# STM32F103ZET6_MinSystem.net
KiCad netlist of a schematic drawn in Altium Designer
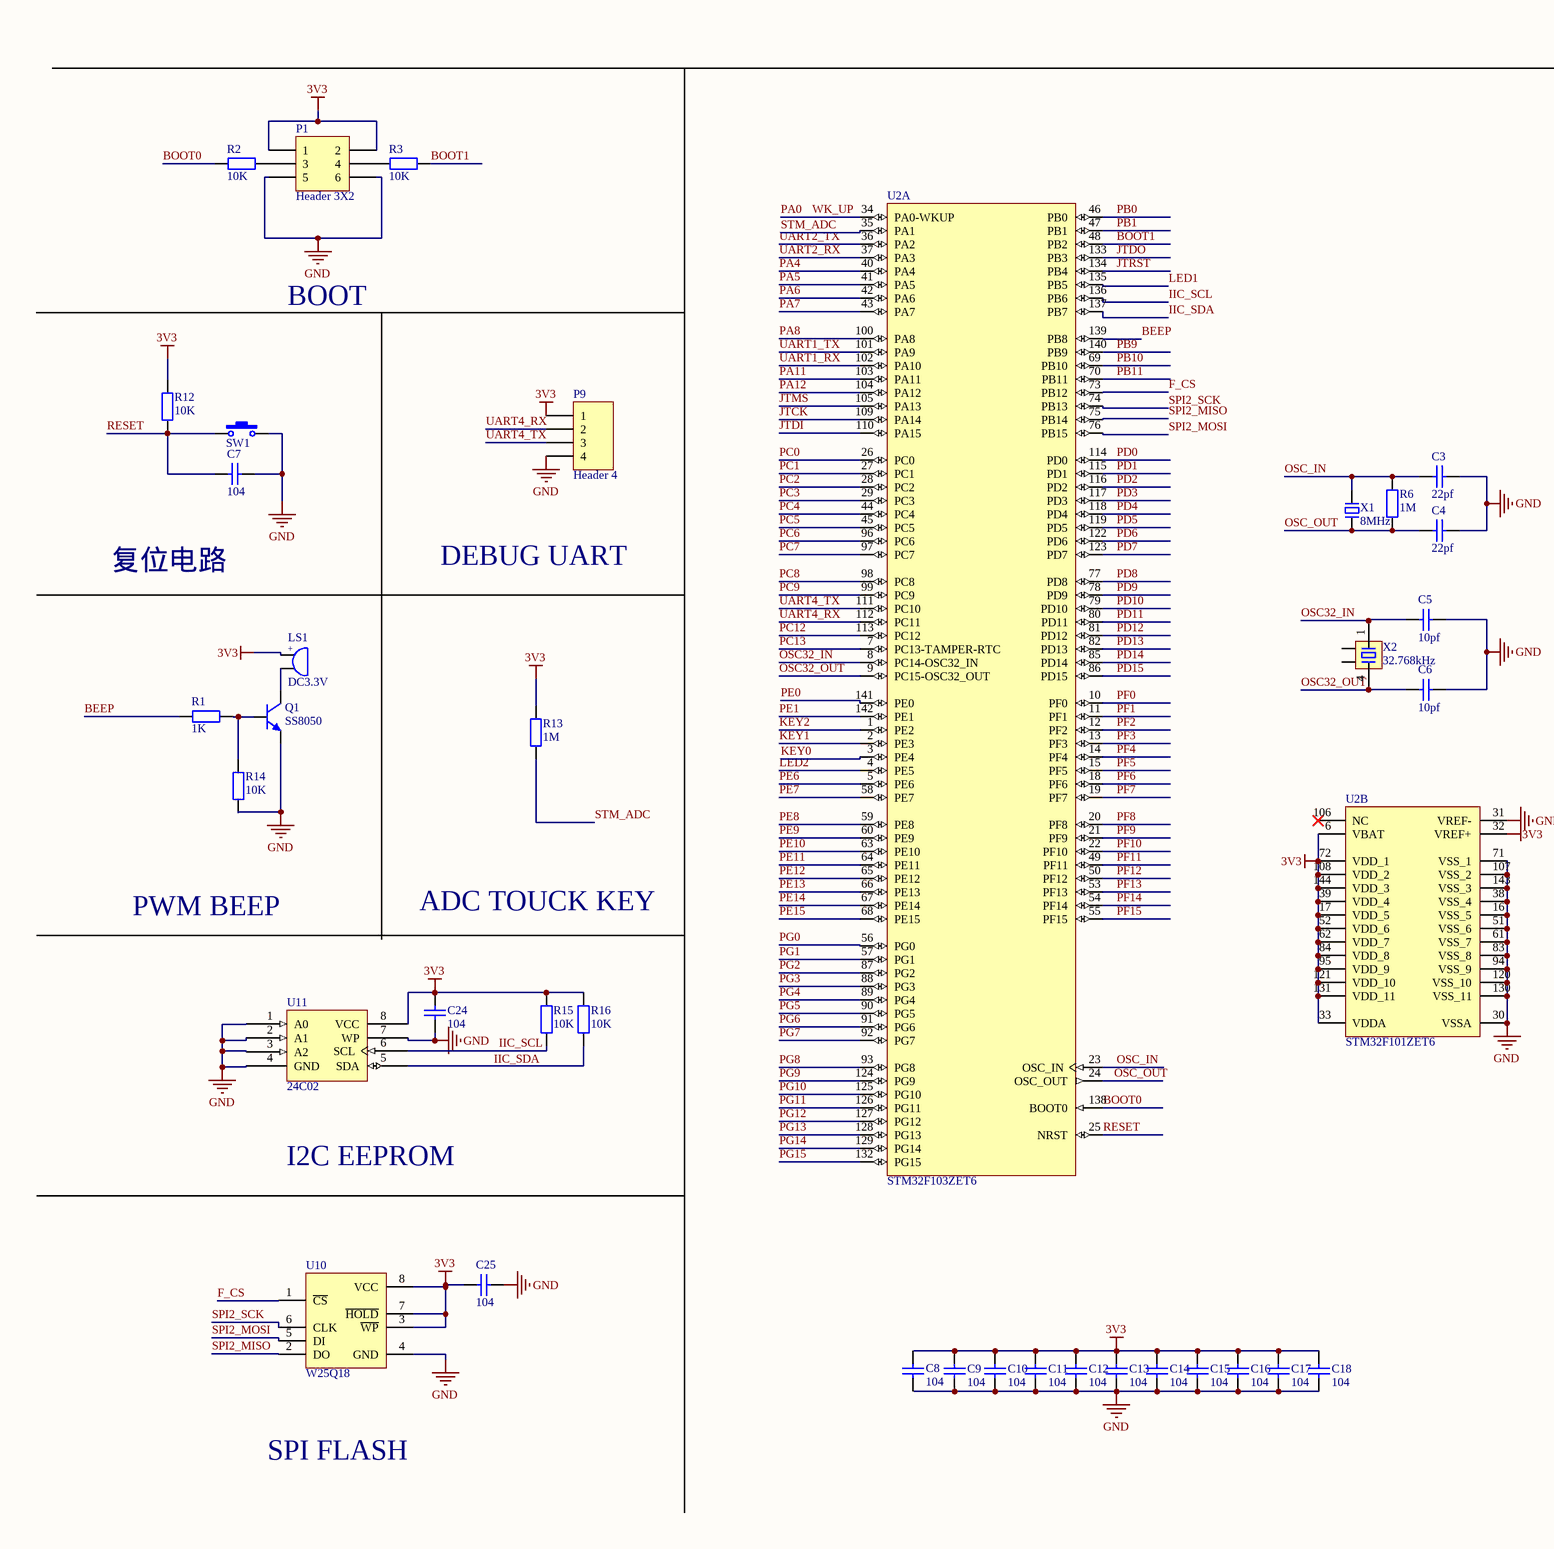
[diagram p0: STM32F103ZET6_MinSystem.SchDoc, left]
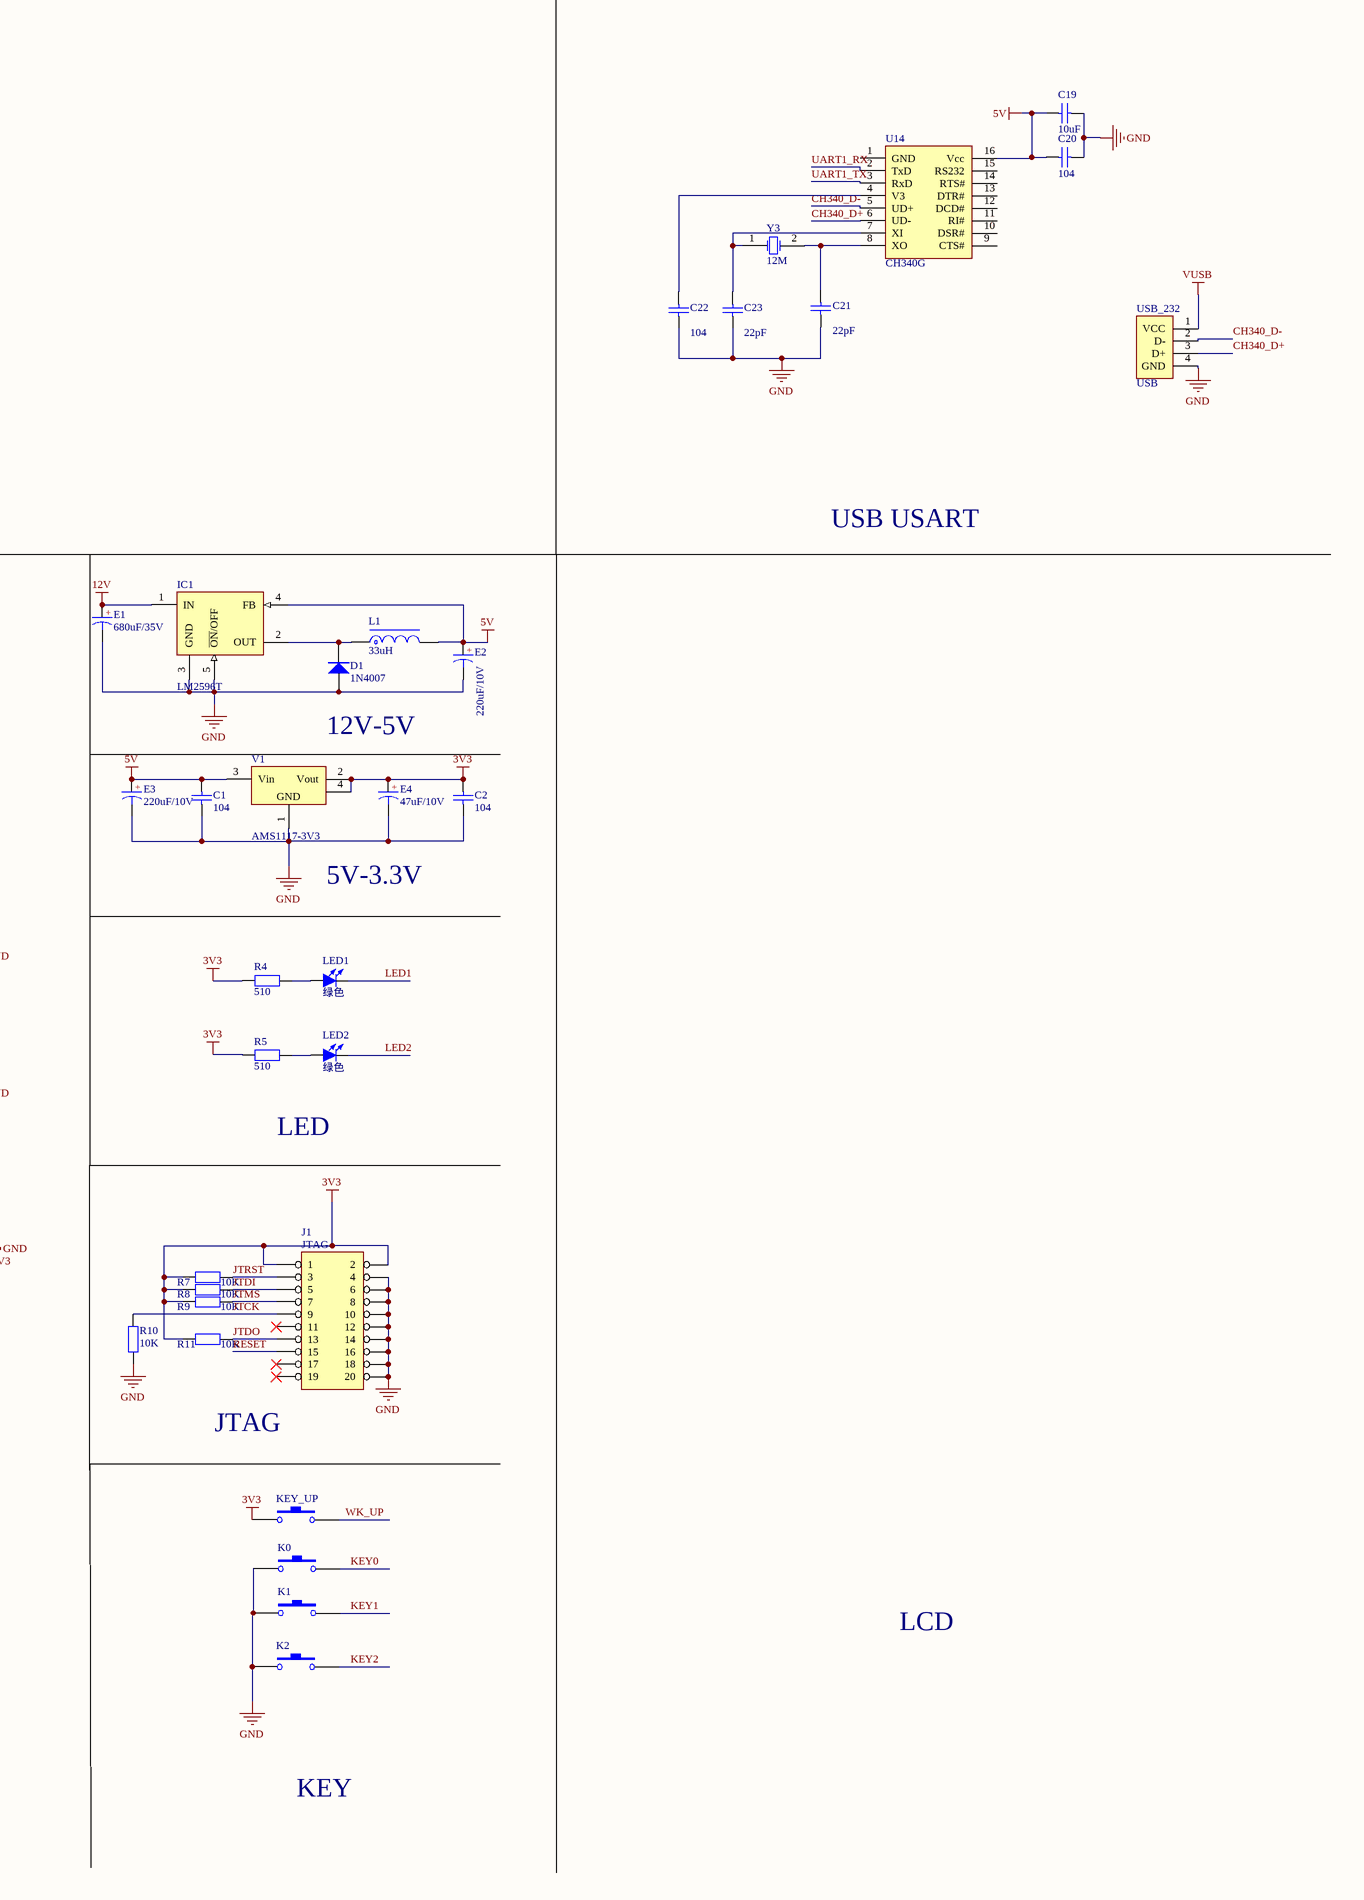
[diagram p1: STM32F103ZET6_MinSystem.SchDoc, right]

(export (version "E")
  (design (tool "Eeschema 10.0.6"))
  (components
    (comp (ref "C1")
      (value "104")
      (footprint "C0603_M")
      (description "贴片电容/MLCC电容")
      (libsource (lib "0.1 - 电阻-电容-电感-晶振-晶体-磁珠-电位器-法拉电容-馈通电容") (part "C"))
    )
    (comp (ref "C2")
      (value "104")
      (footprint "C0603_M")
      (description "贴片电容/MLCC电容")
      (libsource (lib "0.1 - 电阻-电容-电感-晶振-晶体-磁珠-电位器-法拉电容-馈通电容") (part "C"))
    )
    (comp (ref "C3")
      (value "22pf")
      (footprint "C0603_M")
      (description "贴片电容/MLCC电容")
      (libsource (lib "0.1 - 电阻-电容-电感-晶振-晶体-磁珠-电位器-法拉电容-馈通电容") (part "C"))
    )
    (comp (ref "C4")
      (value "22pf")
      (footprint "C0603_M")
      (description "贴片电容/MLCC电容")
      (libsource (lib "0.1 - 电阻-电容-电感-晶振-晶体-磁珠-电位器-法拉电容-馈通电容") (part "C"))
    )
    (comp (ref "C5")
      (value "10pf")
      (footprint "C0603_M")
      (description "贴片电容/MLCC电容")
      (libsource (lib "0.1 - 电阻-电容-电感-晶振-晶体-磁珠-电位器-法拉电容-馈通电容") (part "C"))
    )
    (comp (ref "C6")
      (value "10pf")
      (footprint "C0603_M")
      (description "贴片电容/MLCC电容")
      (libsource (lib "0.1 - 电阻-电容-电感-晶振-晶体-磁珠-电位器-法拉电容-馈通电容") (part "C"))
    )
    (comp (ref "C7")
      (value "104")
      (footprint "C0603_M")
      (description "贴片电容/MLCC电容")
      (libsource (lib "0.1 - 电阻-电容-电感-晶振-晶体-磁珠-电位器-法拉电容-馈通电容") (part "C"))
    )
    (comp (ref "C8")
      (value "104")
      (footprint "C0603_M")
      (description "贴片电容/MLCC电容")
      (libsource (lib "0.1 - 电阻-电容-电感-晶振-晶体-磁珠-电位器-法拉电容-馈通电容") (part "C"))
    )
    (comp (ref "C9")
      (value "104")
      (footprint "C0603_M")
      (description "贴片电容/MLCC电容")
      (libsource (lib "0.1 - 电阻-电容-电感-晶振-晶体-磁珠-电位器-法拉电容-馈通电容") (part "C"))
    )
    (comp (ref "C10")
      (value "104")
      (footprint "C0603_M")
      (description "贴片电容/MLCC电容")
      (libsource (lib "0.1 - 电阻-电容-电感-晶振-晶体-磁珠-电位器-法拉电容-馈通电容") (part "C"))
    )
    (comp (ref "C11")
      (value "104")
      (footprint "C0603_M")
      (description "贴片电容/MLCC电容")
      (libsource (lib "0.1 - 电阻-电容-电感-晶振-晶体-磁珠-电位器-法拉电容-馈通电容") (part "C"))
    )
    (comp (ref "C12")
      (value "104")
      (footprint "C0603_M")
      (description "贴片电容/MLCC电容")
      (libsource (lib "0.1 - 电阻-电容-电感-晶振-晶体-磁珠-电位器-法拉电容-馈通电容") (part "C"))
    )
    (comp (ref "C13")
      (value "104")
      (footprint "C0603_M")
      (description "贴片电容/MLCC电容")
      (libsource (lib "0.1 - 电阻-电容-电感-晶振-晶体-磁珠-电位器-法拉电容-馈通电容") (part "C"))
    )
    (comp (ref "C14")
      (value "104")
      (footprint "C0603_M")
      (description "贴片电容/MLCC电容")
      (libsource (lib "0.1 - 电阻-电容-电感-晶振-晶体-磁珠-电位器-法拉电容-馈通电容") (part "C"))
    )
    (comp (ref "C15")
      (value "104")
      (footprint "C0603_M")
      (description "贴片电容/MLCC电容")
      (libsource (lib "0.1 - 电阻-电容-电感-晶振-晶体-磁珠-电位器-法拉电容-馈通电容") (part "C"))
    )
    (comp (ref "C16")
      (value "104")
      (footprint "C0603_M")
      (description "贴片电容/MLCC电容")
      (libsource (lib "0.1 - 电阻-电容-电感-晶振-晶体-磁珠-电位器-法拉电容-馈通电容") (part "C"))
    )
    (comp (ref "C17")
      (value "104")
      (footprint "C0603_M")
      (description "贴片电容/MLCC电容")
      (libsource (lib "0.1 - 电阻-电容-电感-晶振-晶体-磁珠-电位器-法拉电容-馈通电容") (part "C"))
    )
    (comp (ref "C18")
      (value "104")
      (footprint "C0603_M")
      (description "贴片电容/MLCC电容")
      (libsource (lib "0.1 - 电阻-电容-电感-晶振-晶体-磁珠-电位器-法拉电容-馈通电容") (part "C"))
    )
    (comp (ref "C19")
      (value "10uF")
      (footprint "RAD-0.3")
      (description "Capacitor")
      (fields (field (name "Comment") "Cap") (field (name "PUBLISHER") "Altium Limited"))
      (libsource (lib "Miscellaneous Devices") (part "Cap"))
    )
    (comp (ref "C20")
      (value "104")
      (footprint "RAD-0.3")
      (description "Capacitor")
      (fields (field (name "Comment") "Cap") (field (name "PUBLISHER") "Altium Limited"))
      (libsource (lib "Miscellaneous Devices") (part "Cap"))
    )
    (comp (ref "C21")
      (value "22pF")
      (footprint "RAD-0.3")
      (description "Capacitor")
      (fields (field (name "Comment") "Cap") (field (name "PUBLISHER") "Altium Limited"))
      (libsource (lib "Miscellaneous Devices") (part "Cap"))
    )
    (comp (ref "C22")
      (value "104")
      (footprint "RAD-0.3")
      (description "Capacitor")
      (fields (field (name "Comment") "Cap") (field (name "PUBLISHER") "Altium Limited"))
      (libsource (lib "Miscellaneous Devices") (part "Cap"))
    )
    (comp (ref "C23")
      (value "22pF")
      (footprint "RAD-0.3")
      (description "Capacitor")
      (fields (field (name "Comment") "Cap") (field (name "PUBLISHER") "Altium Limited"))
      (libsource (lib "Miscellaneous Devices") (part "Cap"))
    )
    (comp (ref "C24")
      (value "104")
      (footprint "C0603_M")
      (description "贴片电容/MLCC电容")
      (libsource (lib "0.1 - 电阻-电容-电感-晶振-晶体-磁珠-电位器-法拉电容-馈通电容") (part "C"))
    )
    (comp (ref "C25")
      (value "104")
      (footprint "C0603_M")
      (description "贴片电容/MLCC电容")
      (libsource (lib "0.1 - 电阻-电容-电感-晶振-晶体-磁珠-电位器-法拉电容-馈通电容") (part "C"))
    )
    (comp (ref "D1")
      (value "1N4007")
      (footprint "SMA")
      (description "整流二极管")
      (libsource (lib "0.2 - 二极管-TVS-ESD-整流桥-放电管") (part "1N4007"))
    )
    (comp (ref "E1")
      (value "680uF/35V")
      (footprint "CE G(12.5*13.5)")
      (description "贴片电解电容")
      (libsource (lib "0.1 - 电阻-电容-电感-晶振-晶体-磁珠-电位器-法拉电容-馈通电容") (part "CE_SMD"))
    )
    (comp (ref "E2")
      (value "220uF/10V")
      (footprint "CE D(6.3*7.7)")
      (description "贴片电解电容")
      (libsource (lib "0.1 - 电阻-电容-电感-晶振-晶体-磁珠-电位器-法拉电容-馈通电容") (part "CE_SMD"))
    )
    (comp (ref "E3")
      (value "220uF/10V")
      (footprint "CE D(6.3*7.7)")
      (description "贴片电解电容")
      (libsource (lib "0.1 - 电阻-电容-电感-晶振-晶体-磁珠-电位器-法拉电容-馈通电容") (part "CE_SMD"))
    )
    (comp (ref "E4")
      (value "47uF/10V")
      (footprint "CE B(4*5.4)")
      (description "贴片电解电容")
      (libsource (lib "0.1 - 电阻-电容-电感-晶振-晶体-磁珠-电位器-法拉电容-馈通电容") (part "CE_SMD"))
    )
    (comp (ref "IC1")
      (value "LM2596T")
      (footprint "TO220-5A")
      (description "3A DC-DC降压芯片")
      (libsource (lib "0.7 - 电源类芯片") (part "LM2596T"))
    )
    (comp (ref "J1") (value "JTAG") (footprint "JTAG_20") (libsource (lib "*") (part "HEADER 10X2")))
    (comp (ref "K0")
      (value "SW-PB")
      (footprint "SPST-2")
      (description "Switch")
      (fields (field (name "PUBLISHER") "Altium Limited"))
      (libsource (lib "Miscellaneous Devices") (part "SW-PB"))
    )
    (comp (ref "K1")
      (value "SW-PB")
      (footprint "SPST-2")
      (description "Switch")
      (fields (field (name "PUBLISHER") "Altium Limited"))
      (libsource (lib "Miscellaneous Devices") (part "SW-PB"))
    )
    (comp (ref "K2")
      (value "SW-PB")
      (footprint "SPST-2")
      (description "Switch")
      (fields (field (name "PUBLISHER") "Altium Limited"))
      (libsource (lib "Miscellaneous Devices") (part "SW-PB"))
    )
    (comp (ref "KEY_UP")
      (value "SW-PB")
      (footprint "SPST-2")
      (description "Switch")
      (fields (field (name "PUBLISHER") "Altium Limited"))
      (libsource (lib "Miscellaneous Devices") (part "SW-PB"))
    )
    (comp (ref "L1")
      (value "33uH")
      (footprint "CDRH74")
      (description "CDRH功率屏蔽电感")
      (libsource (lib "0.1 - 电阻-电容-电感-晶振-晶体-磁珠-电位器-法拉电容-馈通电容") (part "L-CDRH"))
    )
    (comp (ref "LED1")
      (value "绿色")
      (footprint "LED0603_G")
      (description "贴片LED")
      (libsource (lib "0.3 - LED发光二极管-IR二极管_接收管-光耦") (part "LED-SMD"))
    )
    (comp (ref "LED2")
      (value "绿色")
      (footprint "LED0603_G")
      (description "贴片LED")
      (libsource (lib "0.3 - LED发光二极管-IR二极管_接收管-光耦") (part "LED-SMD"))
    )
    (comp (ref "LS1")
      (value "DC3.3V")
      (footprint "BEEP 5x9x5.5")
      (description "蜂鸣器")
      (libsource (lib "0.5 - 按键_开关_蜂鸣器_电池_测试点_Mark点_铜柱") (part "BEEP"))
    )
    (comp (ref "P1")
      (value "Header 3X2")
      (footprint "HDR2X3")
      (description "Header, 3-Pin, Dual row")
      (fields (field (name "PUBLISHER") "Altium Limited"))
      (libsource (lib "Miscellaneous Connectors") (part "Header 3X2"))
    )
    (comp (ref "P9")
      (value "Header 4")
      (footprint "HDR1X4")
      (description "Header, 4-Pin")
      (fields (field (name "PUBLISHER") "Altium Limited"))
      (libsource (lib "Miscellaneous Connectors") (part "Header 4"))
    )
    (comp (ref "Q1")
      (value "SS8050")
      (footprint "SOT23-3N")
      (description "高频放大-NPN型")
      (libsource (lib "0.4 - 三极管-场效应管-可控硅") (part "8050-SMD"))
    )
    (comp (ref "R1")
      (value "1K")
      (footprint "R0603_L")
      (description "贴片电阻")
      (libsource (lib "0.1 - 电阻-电容-电感-晶振-晶体-磁珠-电位器-法拉电容-馈通电容") (part "R"))
    )
    (comp (ref "R2")
      (value "10K")
      (footprint "R0603_L")
      (description "贴片电阻")
      (libsource (lib "0.1 - 电阻-电容-电感-晶振-晶体-磁珠-电位器-法拉电容-馈通电容") (part "R"))
    )
    (comp (ref "R3")
      (value "10K")
      (footprint "R0603_L")
      (description "贴片电阻")
      (libsource (lib "0.1 - 电阻-电容-电感-晶振-晶体-磁珠-电位器-法拉电容-馈通电容") (part "R"))
    )
    (comp (ref "R4")
      (value "510")
      (footprint "R0603_L")
      (description "贴片电阻")
      (libsource (lib "0.1 - 电阻-电容-电感-晶振-晶体-磁珠-电位器-法拉电容-馈通电容") (part "R"))
    )
    (comp (ref "R5")
      (value "510")
      (footprint "R0603_L")
      (description "贴片电阻")
      (libsource (lib "0.1 - 电阻-电容-电感-晶振-晶体-磁珠-电位器-法拉电容-馈通电容") (part "R"))
    )
    (comp (ref "R6")
      (value "1M")
      (footprint "R0603_L")
      (description "贴片电阻")
      (libsource (lib "0.1 - 电阻-电容-电感-晶振-晶体-磁珠-电位器-法拉电容-馈通电容") (part "R"))
    )
    (comp (ref "R7")
      (value "10K")
      (footprint "R0603_L")
      (description "贴片电阻")
      (libsource (lib "0.1 - 电阻-电容-电感-晶振-晶体-磁珠-电位器-法拉电容-馈通电容") (part "R"))
    )
    (comp (ref "R8")
      (value "10K")
      (footprint "R0603_L")
      (description "贴片电阻")
      (libsource (lib "0.1 - 电阻-电容-电感-晶振-晶体-磁珠-电位器-法拉电容-馈通电容") (part "R"))
    )
    (comp (ref "R9")
      (value "10K")
      (footprint "R0603_L")
      (description "贴片电阻")
      (libsource (lib "0.1 - 电阻-电容-电感-晶振-晶体-磁珠-电位器-法拉电容-馈通电容") (part "R"))
    )
    (comp (ref "R10")
      (value "10K")
      (footprint "R0603_L")
      (description "贴片电阻")
      (libsource (lib "0.1 - 电阻-电容-电感-晶振-晶体-磁珠-电位器-法拉电容-馈通电容") (part "R"))
    )
    (comp (ref "R11")
      (value "10K")
      (footprint "R0603_L")
      (description "贴片电阻")
      (libsource (lib "0.1 - 电阻-电容-电感-晶振-晶体-磁珠-电位器-法拉电容-馈通电容") (part "R"))
    )
    (comp (ref "R12")
      (value "10K")
      (footprint "R0603_L")
      (description "贴片电阻")
      (libsource (lib "0.1 - 电阻-电容-电感-晶振-晶体-磁珠-电位器-法拉电容-馈通电容") (part "R"))
    )
    (comp (ref "R13")
      (value "1M")
      (footprint "R0603_L")
      (description "贴片电阻")
      (libsource (lib "0.1 - 电阻-电容-电感-晶振-晶体-磁珠-电位器-法拉电容-馈通电容") (part "R"))
    )
    (comp (ref "R14")
      (value "10K")
      (footprint "R0603_L")
      (description "贴片电阻")
      (libsource (lib "0.1 - 电阻-电容-电感-晶振-晶体-磁珠-电位器-法拉电容-馈通电容") (part "R"))
    )
    (comp (ref "R15")
      (value "10K")
      (footprint "R0603_L")
      (description "贴片电阻")
      (libsource (lib "0.1 - 电阻-电容-电感-晶振-晶体-磁珠-电位器-法拉电容-馈通电容") (part "R"))
    )
    (comp (ref "R16")
      (value "10K")
      (footprint "R0603_L")
      (description "贴片电阻")
      (libsource (lib "0.1 - 电阻-电容-电感-晶振-晶体-磁珠-电位器-法拉电容-馈通电容") (part "R"))
    )
    (comp (ref "SW1")
      (value "3x6x5")
      (footprint "SW SMD-3*6*2.5")
      (description "微动开关")
      (libsource (lib "0.5 - 按键_开关_蜂鸣器_保险丝_电池_测试点_Mark点_铜柱") (part "SW-PB"))
    )
    (comp (ref "U2")
      (value "STM32F103ZET6")
      (footprint "LQFP144_N")
      (libsource (lib "2.4 - STM32 F1系列单片机") (part "STM32F101ZET6"))
    )
    (comp (ref "U10")
      (value "W25Q18")
      (footprint "SOP8W_N")
      (description "SPI Flash")
      (libsource (lib "0.8 - 常见芯片") (part "W25Q"))
    )
    (comp (ref "U11")
      (value "24C02")
      (footprint "SOP8_L")
      (description "外置EEPROM")
      (libsource (lib "0.8 - 常见芯片") (part "24Cxx"))
    )
    (comp (ref "U14")
      (value "CH340G")
      (footprint "SOP16_L")
      (description "USB转串口芯片，外置晶振")
      (libsource (lib "0.8 - 常见芯片") (part "CH340G"))
    )
    (comp (ref "USB_232")
      (value "USB")
      (footprint "USB2.0_TYPE-B")
      (description "USB2.0_Type-B母座")
      (libsource (lib "0.6 - 电源_音频_USB Type-C_HDMI_XT60_5557_D-SUB_RJ45_SD-TF_SIM插座") (part "USB2.0_Type-B"))
    )
    (comp (ref "V1")
      (value "AMS1117-3V3")
      (footprint "SOT223_L")
      (description "三端稳压芯片")
      (libsource (lib "0.7 - 电源类芯片") (part "AMS1117"))
    )
    (comp (ref "X1")
      (value "8MHz")
      (footprint "HC-49S")
      (description "2脚无源晶振(谐振器）")
      (libsource (lib "0.1 - 电阻-电容-电感-晶振-晶体-磁珠-电位器-法拉电容-馈通电容") (part "XTAL-2P"))
    )
    (comp (ref "X2")
      (value "32.768kHz")
      (footprint "MC-306")
      (description "MC系列4脚无源晶振(谐振器）")
      (libsource (lib "0.1 - 电阻-电容-电感-晶振-晶体-磁珠-电位器-法拉电容-馈通电容") (part "XTAL-MC-4P"))
    )
    (comp (ref "Y3")
      (value "12M")
      (footprint "R38")
      (description "Crystal Oscillator")
      (fields (field (name "PUBLISHER") "Altium Limited"))
      (libsource (lib "Miscellaneous Devices") (part "XTAL"))
    )
  )
  (nets
    (net (code "1") (name "/BEEP") (class "Default")
      (node (ref "R1") (pin "2") (pinfunction "2_2") (pintype "passive"))
      (node (ref "U2") (pin "139") (pinfunction "PB8_139") (pintype "bidirectional"))
    )
    (net (code "2") (name "/BOOT0") (class "Default")
      (node (ref "R2") (pin "1") (pinfunction "1_1") (pintype "passive"))
      (node (ref "U2") (pin "138") (pinfunction "BOOT0_138") (pintype "input"))
    )
    (net (code "3") (name "/BOOT1") (class "Default")
      (node (ref "R3") (pin "1") (pinfunction "1_1") (pintype "passive"))
      (node (ref "U2") (pin "48") (pinfunction "PB2_48") (pintype "bidirectional"))
    )
    (net (code "4") (name "/CH340_D+") (class "Default")
      (node (ref "U14") (pin "6") (pinfunction "UD-_6") (pintype "passive"))
      (node (ref "USB_232") (pin "3") (pinfunction "D+_3") (pintype "passive"))
    )
    (net (code "5") (name "/CH340_D-") (class "Default")
      (node (ref "U14") (pin "5") (pinfunction "UD+_5") (pintype "passive"))
      (node (ref "USB_232") (pin "2") (pinfunction "D-_2") (pintype "passive"))
    )
    (net (code "6") (name "/F_CS") (class "Default")
      (node (ref "U10") (pin "1") (pinfunction "~{CS}_1") (pintype "passive"))
      (node (ref "U2") (pin "73") (pinfunction "PB12_73") (pintype "bidirectional"))
    )
    (net (code "7") (name "/IIC_SCL") (class "Default")
      (node (ref "R15") (pin "1") (pinfunction "1_1") (pintype "passive"))
      (node (ref "U11") (pin "6") (pinfunction "SCL_6") (pintype "input"))
      (node (ref "U2") (pin "136") (pinfunction "PB6_136") (pintype "bidirectional"))
    )
    (net (code "8") (name "/IIC_SDA") (class "Default")
      (node (ref "U2") (pin "137") (pinfunction "PB7_137") (pintype "bidirectional"))
    )
    (net (code "9") (name "/JTCK") (class "Default")
      (node (ref "J1") (pin "9") (pinfunction "9_9") (pintype "passive"))
      (node (ref "R10") (pin "2") (pinfunction "2_2") (pintype "passive"))
      (node (ref "U2") (pin "109") (pinfunction "PA14_109") (pintype "bidirectional"))
    )
    (net (code "10") (name "/JTDI") (class "Default")
      (node (ref "J1") (pin "5") (pinfunction "5_5") (pintype "passive"))
      (node (ref "R8") (pin "2") (pinfunction "2_2") (pintype "passive"))
      (node (ref "U2") (pin "110") (pinfunction "PA15_110") (pintype "bidirectional"))
    )
    (net (code "11") (name "/JTDO") (class "Default")
      (node (ref "J1") (pin "13") (pinfunction "13_13") (pintype "passive"))
      (node (ref "R11") (pin "2") (pinfunction "2_2") (pintype "passive"))
      (node (ref "U2") (pin "133") (pinfunction "PB3_133") (pintype "bidirectional"))
    )
    (net (code "12") (name "/JTMS") (class "Default")
      (node (ref "J1") (pin "7") (pinfunction "7_7") (pintype "passive"))
      (node (ref "R9") (pin "2") (pinfunction "2_2") (pintype "passive"))
      (node (ref "U2") (pin "105") (pinfunction "PA13_105") (pintype "bidirectional"))
    )
    (net (code "13") (name "/JTRST") (class "Default")
      (node (ref "J1") (pin "3") (pinfunction "3_3") (pintype "passive"))
      (node (ref "R7") (pin "2") (pinfunction "2_2") (pintype "passive"))
      (node (ref "U2") (pin "134") (pinfunction "PB4_134") (pintype "bidirectional"))
    )
    (net (code "14") (name "/KEY0") (class "Default")
      (node (ref "K0") (pin "2") (pinfunction "2_2") (pintype "passive"))
      (node (ref "U2") (pin "3") (pinfunction "PE4_3") (pintype "bidirectional"))
    )
    (net (code "15") (name "/KEY1") (class "Default")
      (node (ref "K1") (pin "2") (pinfunction "2_2") (pintype "passive"))
      (node (ref "U2") (pin "2") (pinfunction "PE3_2") (pintype "bidirectional"))
    )
    (net (code "16") (name "/KEY2") (class "Default")
      (node (ref "K2") (pin "2") (pinfunction "2_2") (pintype "passive"))
      (node (ref "U2") (pin "1") (pinfunction "PE2_1") (pintype "bidirectional"))
    )
    (net (code "17") (name "/LED1") (class "Default")
      (node (ref "LED1") (pin "2") (pinfunction "K_2") (pintype "passive"))
      (node (ref "U2") (pin "135") (pinfunction "PB5_135") (pintype "bidirectional"))
    )
    (net (code "18") (name "/LED2") (class "Default")
      (node (ref "LED2") (pin "2") (pinfunction "K_2") (pintype "passive"))
      (node (ref "U2") (pin "4") (pinfunction "PE5_4") (pintype "bidirectional"))
    )
    (net (code "19") (name "/OSC32_IN") (class "Default")
      (node (ref "C5") (pin "1") (pinfunction "1_1") (pintype "passive"))
      (node (ref "U2") (pin "8") (pinfunction "PC14-OSC32_IN_8") (pintype "bidirectional"))
      (node (ref "X2") (pin "1") (pinfunction "1_1") (pintype "passive"))
    )
    (net (code "20") (name "/OSC32_OUT") (class "Default")
      (node (ref "C6") (pin "1") (pinfunction "1_1") (pintype "passive"))
      (node (ref "U2") (pin "9") (pinfunction "PC15-OSC32_OUT_9") (pintype "bidirectional"))
      (node (ref "X2") (pin "4") (pinfunction "4_4") (pintype "passive"))
    )
    (net (code "21") (name "/OSC_IN") (class "Default")
      (node (ref "C3") (pin "1") (pinfunction "1_1") (pintype "passive"))
      (node (ref "R6") (pin "2") (pinfunction "2_2") (pintype "passive"))
      (node (ref "U2") (pin "23") (pinfunction "OSC_IN_23") (pintype "input"))
      (node (ref "X1") (pin "1") (pinfunction "1_1") (pintype "passive"))
    )
    (net (code "22") (name "/OSC_OUT") (class "Default")
      (node (ref "C4") (pin "1") (pinfunction "1_1") (pintype "passive"))
      (node (ref "R6") (pin "1") (pinfunction "1_1") (pintype "passive"))
      (node (ref "U2") (pin "24") (pinfunction "OSC_OUT_24") (pintype "output"))
      (node (ref "X1") (pin "2") (pinfunction "2_2") (pintype "passive"))
    )
    (net (code "23") (name "/PA0") (class "Default")
      (node (ref "KEY_UP") (pin "2") (pinfunction "2_2") (pintype "passive"))
      (node (ref "U2") (pin "34") (pinfunction "PA0-WKUP_34") (pintype "bidirectional"))
    )
    (net (code "24") (name "/PA4") (class "Default")
      (node (ref "U2") (pin "40") (pinfunction "PA4_40") (pintype "bidirectional"))
    )
    (net (code "25") (name "/PA5") (class "Default")
      (node (ref "U2") (pin "41") (pinfunction "PA5_41") (pintype "bidirectional"))
    )
    (net (code "26") (name "/PA6") (class "Default")
      (node (ref "U2") (pin "42") (pinfunction "PA6_42") (pintype "bidirectional"))
    )
    (net (code "27") (name "/PA7") (class "Default")
      (node (ref "U2") (pin "43") (pinfunction "PA7_43") (pintype "bidirectional"))
    )
    (net (code "28") (name "/PA8") (class "Default")
      (node (ref "U2") (pin "100") (pinfunction "PA8_100") (pintype "bidirectional"))
    )
    (net (code "29") (name "/PA11") (class "Default")
      (node (ref "U2") (pin "103") (pinfunction "PA11_103") (pintype "bidirectional"))
    )
    (net (code "30") (name "/PA12") (class "Default")
      (node (ref "U2") (pin "104") (pinfunction "PA12_104") (pintype "bidirectional"))
    )
    (net (code "31") (name "/PB0") (class "Default")
      (node (ref "U2") (pin "46") (pinfunction "PB0_46") (pintype "bidirectional"))
    )
    (net (code "32") (name "/PB1") (class "Default")
      (node (ref "U2") (pin "47") (pinfunction "PB1_47") (pintype "bidirectional"))
    )
    (net (code "33") (name "/PB9") (class "Default")
      (node (ref "U2") (pin "140") (pinfunction "PB9_140") (pintype "bidirectional"))
    )
    (net (code "34") (name "/PB10") (class "Default")
      (node (ref "U2") (pin "69") (pinfunction "PB10_69") (pintype "bidirectional"))
    )
    (net (code "35") (name "/PB11") (class "Default")
      (node (ref "U2") (pin "70") (pinfunction "PB11_70") (pintype "bidirectional"))
    )
    (net (code "36") (name "/PC0") (class "Default")
      (node (ref "U2") (pin "26") (pinfunction "PC0_26") (pintype "bidirectional"))
    )
    (net (code "37") (name "/PC1") (class "Default")
      (node (ref "U2") (pin "27") (pinfunction "PC1_27") (pintype "bidirectional"))
    )
    (net (code "38") (name "/PC2") (class "Default")
      (node (ref "U2") (pin "28") (pinfunction "PC2_28") (pintype "bidirectional"))
    )
    (net (code "39") (name "/PC3") (class "Default")
      (node (ref "U2") (pin "29") (pinfunction "PC3_29") (pintype "bidirectional"))
    )
    (net (code "40") (name "/PC4") (class "Default")
      (node (ref "U2") (pin "44") (pinfunction "PC4_44") (pintype "bidirectional"))
    )
    (net (code "41") (name "/PC5") (class "Default")
      (node (ref "U2") (pin "45") (pinfunction "PC5_45") (pintype "bidirectional"))
    )
    (net (code "42") (name "/PC6") (class "Default")
      (node (ref "U2") (pin "96") (pinfunction "PC6_96") (pintype "bidirectional"))
    )
    (net (code "43") (name "/PC7") (class "Default")
      (node (ref "U2") (pin "97") (pinfunction "PC7_97") (pintype "bidirectional"))
    )
    (net (code "44") (name "/PC8") (class "Default")
      (node (ref "U2") (pin "98") (pinfunction "PC8_98") (pintype "bidirectional"))
    )
    (net (code "45") (name "/PC9") (class "Default")
      (node (ref "U2") (pin "99") (pinfunction "PC9_99") (pintype "bidirectional"))
    )
    (net (code "46") (name "/PC12") (class "Default")
      (node (ref "U2") (pin "113") (pinfunction "PC12_113") (pintype "bidirectional"))
    )
    (net (code "47") (name "/PC13") (class "Default")
      (node (ref "U2") (pin "7") (pinfunction "PC13-TAMPER-RTC_7") (pintype "bidirectional"))
    )
    (net (code "48") (name "/PD0") (class "Default")
      (node (ref "U2") (pin "114") (pinfunction "PD0_114") (pintype "bidirectional"))
    )
    (net (code "49") (name "/PD1") (class "Default")
      (node (ref "U2") (pin "115") (pinfunction "PD1_115") (pintype "bidirectional"))
    )
    (net (code "50") (name "/PD2") (class "Default")
      (node (ref "U2") (pin "116") (pinfunction "PD2_116") (pintype "bidirectional"))
    )
    (net (code "51") (name "/PD3") (class "Default")
      (node (ref "U2") (pin "117") (pinfunction "PD3_117") (pintype "bidirectional"))
    )
    (net (code "52") (name "/PD4") (class "Default")
      (node (ref "U2") (pin "118") (pinfunction "PD4_118") (pintype "bidirectional"))
    )
    (net (code "53") (name "/PD5") (class "Default")
      (node (ref "U2") (pin "119") (pinfunction "PD5_119") (pintype "bidirectional"))
    )
    (net (code "54") (name "/PD6") (class "Default")
      (node (ref "U2") (pin "122") (pinfunction "PD6_122") (pintype "bidirectional"))
    )
    (net (code "55") (name "/PD7") (class "Default")
      (node (ref "U2") (pin "123") (pinfunction "PD7_123") (pintype "bidirectional"))
    )
    (net (code "56") (name "/PD8") (class "Default")
      (node (ref "U2") (pin "77") (pinfunction "PD8_77") (pintype "bidirectional"))
    )
    (net (code "57") (name "/PD9") (class "Default")
      (node (ref "U2") (pin "78") (pinfunction "PD9_78") (pintype "bidirectional"))
    )
    (net (code "58") (name "/PD10") (class "Default")
      (node (ref "U2") (pin "79") (pinfunction "PD10_79") (pintype "bidirectional"))
    )
    (net (code "59") (name "/PD11") (class "Default")
      (node (ref "U2") (pin "80") (pinfunction "PD11_80") (pintype "bidirectional"))
    )
    (net (code "60") (name "/PD12") (class "Default")
      (node (ref "U2") (pin "81") (pinfunction "PD12_81") (pintype "bidirectional"))
    )
    (net (code "61") (name "/PD13") (class "Default")
      (node (ref "U2") (pin "82") (pinfunction "PD13_82") (pintype "bidirectional"))
    )
    (net (code "62") (name "/PD14") (class "Default")
      (node (ref "U2") (pin "85") (pinfunction "PD14_85") (pintype "bidirectional"))
    )
    (net (code "63") (name "/PD15") (class "Default")
      (node (ref "U2") (pin "86") (pinfunction "PD15_86") (pintype "bidirectional"))
    )
    (net (code "64") (name "/PE0") (class "Default")
      (node (ref "U2") (pin "141") (pinfunction "PE0_141") (pintype "bidirectional"))
    )
    (net (code "65") (name "/PE1") (class "Default")
      (node (ref "U2") (pin "142") (pinfunction "PE1_142") (pintype "bidirectional"))
    )
    (net (code "66") (name "/PE6") (class "Default")
      (node (ref "U2") (pin "5") (pinfunction "PE6_5") (pintype "bidirectional"))
    )
    (net (code "67") (name "/PE7") (class "Default")
      (node (ref "U2") (pin "58") (pinfunction "PE7_58") (pintype "bidirectional"))
    )
    (net (code "68") (name "/PE8") (class "Default")
      (node (ref "U2") (pin "59") (pinfunction "PE8_59") (pintype "bidirectional"))
    )
    (net (code "69") (name "/PE9") (class "Default")
      (node (ref "U2") (pin "60") (pinfunction "PE9_60") (pintype "bidirectional"))
    )
    (net (code "70") (name "/PE10") (class "Default")
      (node (ref "U2") (pin "63") (pinfunction "PE10_63") (pintype "bidirectional"))
    )
    (net (code "71") (name "/PE11") (class "Default")
      (node (ref "U2") (pin "64") (pinfunction "PE11_64") (pintype "bidirectional"))
    )
    (net (code "72") (name "/PE12") (class "Default")
      (node (ref "U2") (pin "65") (pinfunction "PE12_65") (pintype "bidirectional"))
    )
    (net (code "73") (name "/PE13") (class "Default")
      (node (ref "U2") (pin "66") (pinfunction "PE13_66") (pintype "bidirectional"))
    )
    (net (code "74") (name "/PE14") (class "Default")
      (node (ref "U2") (pin "67") (pinfunction "PE14_67") (pintype "bidirectional"))
    )
    (net (code "75") (name "/PE15") (class "Default")
      (node (ref "U2") (pin "68") (pinfunction "PE15_68") (pintype "bidirectional"))
    )
    (net (code "76") (name "/PF0") (class "Default")
      (node (ref "U2") (pin "10") (pinfunction "PF0_10") (pintype "bidirectional"))
    )
    (net (code "77") (name "/PF1") (class "Default")
      (node (ref "U2") (pin "11") (pinfunction "PF1_11") (pintype "bidirectional"))
    )
    (net (code "78") (name "/PF2") (class "Default")
      (node (ref "U2") (pin "12") (pinfunction "PF2_12") (pintype "bidirectional"))
    )
    (net (code "79") (name "/PF3") (class "Default")
      (node (ref "U2") (pin "13") (pinfunction "PF3_13") (pintype "bidirectional"))
    )
    (net (code "80") (name "/PF4") (class "Default")
      (node (ref "U2") (pin "14") (pinfunction "PF4_14") (pintype "bidirectional"))
    )
    (net (code "81") (name "/PF5") (class "Default")
      (node (ref "U2") (pin "15") (pinfunction "PF5_15") (pintype "bidirectional"))
    )
    (net (code "82") (name "/PF6") (class "Default")
      (node (ref "U2") (pin "18") (pinfunction "PF6_18") (pintype "bidirectional"))
    )
    (net (code "83") (name "/PF7") (class "Default")
      (node (ref "U2") (pin "19") (pinfunction "PF7_19") (pintype "bidirectional"))
    )
    (net (code "84") (name "/PF8") (class "Default")
      (node (ref "U2") (pin "20") (pinfunction "PF8_20") (pintype "bidirectional"))
    )
    (net (code "85") (name "/PF9") (class "Default")
      (node (ref "U2") (pin "21") (pinfunction "PF9_21") (pintype "bidirectional"))
    )
    (net (code "86") (name "/PF10") (class "Default")
      (node (ref "U2") (pin "22") (pinfunction "PF10_22") (pintype "bidirectional"))
    )
    (net (code "87") (name "/PF11") (class "Default")
      (node (ref "U2") (pin "49") (pinfunction "PF11_49") (pintype "bidirectional"))
    )
    (net (code "88") (name "/PF12") (class "Default")
      (node (ref "U2") (pin "50") (pinfunction "PF12_50") (pintype "bidirectional"))
    )
    (net (code "89") (name "/PF13") (class "Default")
      (node (ref "U2") (pin "53") (pinfunction "PF13_53") (pintype "bidirectional"))
    )
    (net (code "90") (name "/PF14") (class "Default")
      (node (ref "U2") (pin "54") (pinfunction "PF14_54") (pintype "bidirectional"))
    )
    (net (code "91") (name "/PF15") (class "Default")
      (node (ref "U2") (pin "55") (pinfunction "PF15_55") (pintype "bidirectional"))
    )
    (net (code "92") (name "/PG0") (class "Default")
      (node (ref "U2") (pin "56") (pinfunction "PG0_56") (pintype "bidirectional"))
    )
    (net (code "93") (name "/PG1") (class "Default")
      (node (ref "U2") (pin "57") (pinfunction "PG1_57") (pintype "bidirectional"))
    )
    (net (code "94") (name "/PG2") (class "Default")
      (node (ref "U2") (pin "87") (pinfunction "PG2_87") (pintype "bidirectional"))
    )
    (net (code "95") (name "/PG3") (class "Default")
      (node (ref "U2") (pin "88") (pinfunction "PG3_88") (pintype "bidirectional"))
    )
    (net (code "96") (name "/PG4") (class "Default")
      (node (ref "U2") (pin "89") (pinfunction "PG4_89") (pintype "bidirectional"))
    )
    (net (code "97") (name "/PG5") (class "Default")
      (node (ref "U2") (pin "90") (pinfunction "PG5_90") (pintype "bidirectional"))
    )
    (net (code "98") (name "/PG6") (class "Default")
      (node (ref "U2") (pin "91") (pinfunction "PG6_91") (pintype "bidirectional"))
    )
    (net (code "99") (name "/PG7") (class "Default")
      (node (ref "U2") (pin "92") (pinfunction "PG7_92") (pintype "bidirectional"))
    )
    (net (code "100") (name "/PG8") (class "Default")
      (node (ref "U2") (pin "93") (pinfunction "PG8_93") (pintype "bidirectional"))
    )
    (net (code "101") (name "/PG9") (class "Default")
      (node (ref "U2") (pin "124") (pinfunction "PG9_124") (pintype "bidirectional"))
    )
    (net (code "102") (name "/PG10") (class "Default")
      (node (ref "U2") (pin "125") (pinfunction "PG10_125") (pintype "bidirectional"))
    )
    (net (code "103") (name "/PG11") (class "Default")
      (node (ref "U2") (pin "126") (pinfunction "PG11_126") (pintype "bidirectional"))
    )
    (net (code "104") (name "/PG12") (class "Default")
      (node (ref "U2") (pin "127") (pinfunction "PG12_127") (pintype "bidirectional"))
    )
    (net (code "105") (name "/PG13") (class "Default")
      (node (ref "U2") (pin "128") (pinfunction "PG13_128") (pintype "bidirectional"))
    )
    (net (code "106") (name "/PG14") (class "Default")
      (node (ref "U2") (pin "129") (pinfunction "PG14_129") (pintype "bidirectional"))
    )
    (net (code "107") (name "/PG15") (class "Default")
      (node (ref "U2") (pin "132") (pinfunction "PG15_132") (pintype "bidirectional"))
    )
    (net (code "108") (name "/RESET") (class "Default")
      (node (ref "C7") (pin "1") (pinfunction "1_1") (pintype "passive"))
      (node (ref "J1") (pin "15") (pinfunction "15_15") (pintype "passive"))
      (node (ref "R12") (pin "1") (pinfunction "1_1") (pintype "passive"))
      (node (ref "SW1") (pin "1") (pinfunction "1_1") (pintype "passive"))
      (node (ref "U2") (pin "25") (pinfunction "NRST_25") (pintype "bidirectional"))
    )
    (net (code "109") (name "/SPI2_MISO") (class "Default")
      (node (ref "U10") (pin "2") (pinfunction "DO_2") (pintype "passive"))
      (node (ref "U2") (pin "75") (pinfunction "PB14_75") (pintype "bidirectional"))
    )
    (net (code "110") (name "/SPI2_MOSI") (class "Default")
      (node (ref "U10") (pin "5") (pinfunction "DI_5") (pintype "passive"))
      (node (ref "U2") (pin "76") (pinfunction "PB15_76") (pintype "bidirectional"))
    )
    (net (code "111") (name "/SPI2_SCK") (class "Default")
      (node (ref "U10") (pin "6") (pinfunction "CLK_6") (pintype "passive"))
      (node (ref "U2") (pin "74") (pinfunction "PB13_74") (pintype "bidirectional"))
    )
    (net (code "112") (name "/STM_ADC") (class "Default")
      (node (ref "R13") (pin "1") (pinfunction "1_1") (pintype "passive"))
      (node (ref "U2") (pin "35") (pinfunction "PA1_35") (pintype "bidirectional"))
    )
    (net (code "113") (name "/UART1_RX") (class "Default")
      (node (ref "U14") (pin "2") (pinfunction "TxD_2") (pintype "passive"))
      (node (ref "U2") (pin "102") (pinfunction "PA10_102") (pintype "bidirectional"))
    )
    (net (code "114") (name "/UART1_TX") (class "Default")
      (node (ref "U14") (pin "3") (pinfunction "RxD_3") (pintype "passive"))
      (node (ref "U2") (pin "101") (pinfunction "PA9_101") (pintype "bidirectional"))
    )
    (net (code "115") (name "/UART2_RX") (class "Default")
      (node (ref "U2") (pin "37") (pinfunction "PA3_37") (pintype "bidirectional"))
    )
    (net (code "116") (name "/UART2_TX") (class "Default")
      (node (ref "U2") (pin "36") (pinfunction "PA2_36") (pintype "bidirectional"))
    )
    (net (code "117") (name "/UART4_RX") (class "Default")
      (node (ref "P9") (pin "2") (pinfunction "2_2") (pintype "passive"))
      (node (ref "U2") (pin "112") (pinfunction "PC11_112") (pintype "bidirectional"))
    )
    (net (code "118") (name "/UART4_TX") (class "Default")
      (node (ref "P9") (pin "3") (pinfunction "3_3") (pintype "passive"))
      (node (ref "U2") (pin "111") (pinfunction "PC10_111") (pintype "bidirectional"))
    )
    (net (code "119") (name "3V3") (class "Default")
      (node (ref "C10") (pin "2") (pinfunction "2_2") (pintype "passive"))
      (node (ref "C11") (pin "2") (pinfunction "2_2") (pintype "passive"))
      (node (ref "C12") (pin "2") (pinfunction "2_2") (pintype "passive"))
      (node (ref "C13") (pin "2") (pinfunction "2_2") (pintype "passive"))
      (node (ref "C14") (pin "2") (pinfunction "2_2") (pintype "passive"))
      (node (ref "C15") (pin "2") (pinfunction "2_2") (pintype "passive"))
      (node (ref "C16") (pin "2") (pinfunction "2_2") (pintype "passive"))
      (node (ref "C17") (pin "2") (pinfunction "2_2") (pintype "passive"))
      (node (ref "C18") (pin "2") (pinfunction "2_2") (pintype "passive"))
      (node (ref "C2") (pin "2") (pinfunction "2_2") (pintype "passive"))
      (node (ref "C24") (pin "1") (pinfunction "1_1") (pintype "passive"))
      (node (ref "C25") (pin "2") (pinfunction "2_2") (pintype "passive"))
      (node (ref "C9") (pin "2") (pinfunction "2_2") (pintype "passive"))
      (node (ref "E4") (pin "1") (pinfunction "1_1") (pintype "passive"))
      (node (ref "J1") (pin "1") (pinfunction "1_1") (pintype "passive"))
      (node (ref "J1") (pin "2") (pinfunction "2_2") (pintype "passive"))
      (node (ref "KEY_UP") (pin "1") (pinfunction "1_1") (pintype "passive"))
      (node (ref "LS1") (pin "1") (pinfunction "1_1") (pintype "passive"))
      (node (ref "P1") (pin "1") (pinfunction "1_1") (pintype "passive"))
      (node (ref "P1") (pin "2") (pinfunction "2_2") (pintype "passive"))
      (node (ref "P9") (pin "1") (pinfunction "1_1") (pintype "passive"))
      (node (ref "R11") (pin "1") (pinfunction "1_1") (pintype "passive"))
      (node (ref "R12") (pin "2") (pinfunction "2_2") (pintype "passive"))
      (node (ref "R13") (pin "2") (pinfunction "2_2") (pintype "passive"))
      (node (ref "R15") (pin "2") (pinfunction "2_2") (pintype "passive"))
      (node (ref "R16") (pin "2") (pinfunction "2_2") (pintype "passive"))
      (node (ref "R4") (pin "1") (pinfunction "1_1") (pintype "passive"))
      (node (ref "R5") (pin "1") (pinfunction "1_1") (pintype "passive"))
      (node (ref "R7") (pin "1") (pinfunction "1_1") (pintype "passive"))
      (node (ref "R8") (pin "1") (pinfunction "1_1") (pintype "passive"))
      (node (ref "R9") (pin "1") (pinfunction "1_1") (pintype "passive"))
      (node (ref "U10") (pin "3") (pinfunction "~{WP}_3") (pintype "passive"))
      (node (ref "U10") (pin "7") (pinfunction "~{HOLD}_7") (pintype "passive"))
      (node (ref "U10") (pin "8") (pinfunction "VCC_8") (pintype "passive"))
      (node (ref "U11") (pin "8") (pinfunction "VCC_8") (pintype "power_in"))
      (node (ref "U2") (pin "108") (pinfunction "VDD_2_108") (pintype "power_in"))
      (node (ref "U2") (pin "121") (pinfunction "VDD_10_121") (pintype "power_in"))
      (node (ref "U2") (pin "131") (pinfunction "VDD_11_131") (pintype "power_in"))
      (node (ref "U2") (pin "144") (pinfunction "VDD_3_144") (pintype "power_in"))
      (node (ref "U2") (pin "17") (pinfunction "VDD_5_17") (pintype "power_in"))
      (node (ref "U2") (pin "32") (pinfunction "VREF+_32") (pintype "power_in"))
      (node (ref "U2") (pin "33") (pinfunction "VDDA_33") (pintype "power_in"))
      (node (ref "U2") (pin "39") (pinfunction "VDD_4_39") (pintype "power_in"))
      (node (ref "U2") (pin "52") (pinfunction "VDD_6_52") (pintype "power_in"))
      (node (ref "U2") (pin "6") (pinfunction "VBAT_6") (pintype "power_in"))
      (node (ref "U2") (pin "62") (pinfunction "VDD_7_62") (pintype "power_in"))
      (node (ref "U2") (pin "72") (pinfunction "VDD_1_72") (pintype "power_in"))
      (node (ref "U2") (pin "84") (pinfunction "VDD_8_84") (pintype "power_in"))
      (node (ref "U2") (pin "95") (pinfunction "VDD_9_95") (pintype "power_in"))
      (node (ref "V1") (pin "2") (pinfunction "Vout_2") (pintype "passive"))
      (node (ref "V1") (pin "4") (pinfunction "GND_4") (pintype "passive"))
    )
    (net (code "120") (name "5V") (class "Default")
      (node (ref "C1") (pin "2") (pinfunction "2_2") (pintype "passive"))
      (node (ref "C19") (pin "2") (pinfunction "2_2") (pintype "passive"))
      (node (ref "C20") (pin "2") (pinfunction "2_2") (pintype "passive"))
      (node (ref "E2") (pin "1") (pinfunction "1_1") (pintype "passive"))
      (node (ref "E3") (pin "1") (pinfunction "1_1") (pintype "passive"))
      (node (ref "IC1") (pin "4") (pinfunction "FB_4") (pintype "input"))
      (node (ref "L1") (pin "2") (pinfunction "2_2") (pintype "passive"))
      (node (ref "U14") (pin "16") (pinfunction "Vcc_16") (pintype "passive"))
      (node (ref "V1") (pin "3") (pinfunction "Vin_3") (pintype "passive"))
    )
    (net (code "121") (name "12V") (class "Default")
      (node (ref "E1") (pin "1") (pinfunction "1_1") (pintype "passive"))
      (node (ref "IC1") (pin "1") (pinfunction "IN_1") (pintype "power_in"))
    )
    (net (code "122") (name "GND") (class "Default")
      (node (ref "C1") (pin "1") (pinfunction "1_1") (pintype "passive"))
      (node (ref "C10") (pin "1") (pinfunction "1_1") (pintype "passive"))
      (node (ref "C11") (pin "1") (pinfunction "1_1") (pintype "passive"))
      (node (ref "C12") (pin "1") (pinfunction "1_1") (pintype "passive"))
      (node (ref "C13") (pin "1") (pinfunction "1_1") (pintype "passive"))
      (node (ref "C14") (pin "1") (pinfunction "1_1") (pintype "passive"))
      (node (ref "C15") (pin "1") (pinfunction "1_1") (pintype "passive"))
      (node (ref "C16") (pin "1") (pinfunction "1_1") (pintype "passive"))
      (node (ref "C17") (pin "1") (pinfunction "1_1") (pintype "passive"))
      (node (ref "C18") (pin "1") (pinfunction "1_1") (pintype "passive"))
      (node (ref "C19") (pin "1") (pinfunction "1_1") (pintype "passive"))
      (node (ref "C2") (pin "1") (pinfunction "1_1") (pintype "passive"))
      (node (ref "C20") (pin "1") (pinfunction "1_1") (pintype "passive"))
      (node (ref "C21") (pin "1") (pinfunction "1_1") (pintype "passive"))
      (node (ref "C22") (pin "1") (pinfunction "1_1") (pintype "passive"))
      (node (ref "C23") (pin "1") (pinfunction "1_1") (pintype "passive"))
      (node (ref "C24") (pin "2") (pinfunction "2_2") (pintype "passive"))
      (node (ref "C25") (pin "1") (pinfunction "1_1") (pintype "passive"))
      (node (ref "C3") (pin "2") (pinfunction "2_2") (pintype "passive"))
      (node (ref "C4") (pin "2") (pinfunction "2_2") (pintype "passive"))
      (node (ref "C5") (pin "2") (pinfunction "2_2") (pintype "passive"))
      (node (ref "C6") (pin "2") (pinfunction "2_2") (pintype "passive"))
      (node (ref "C7") (pin "2") (pinfunction "2_2") (pintype "passive"))
      (node (ref "C9") (pin "1") (pinfunction "1_1") (pintype "passive"))
      (node (ref "D1") (pin "1") (pinfunction "A_1") (pintype "passive"))
      (node (ref "E1") (pin "2") (pinfunction "2_2") (pintype "passive"))
      (node (ref "E2") (pin "2") (pinfunction "2_2") (pintype "passive"))
      (node (ref "E3") (pin "2") (pinfunction "2_2") (pintype "passive"))
      (node (ref "E4") (pin "2") (pinfunction "2_2") (pintype "passive"))
      (node (ref "IC1") (pin "3") (pinfunction "GND_3") (pintype "power_in"))
      (node (ref "IC1") (pin "5") (pinfunction "~{ON}/OFF_5") (pintype "input"))
      (node (ref "J1") (pin "10") (pinfunction "10_10") (pintype "passive"))
      (node (ref "J1") (pin "12") (pinfunction "12_12") (pintype "passive"))
      (node (ref "J1") (pin "14") (pinfunction "14_14") (pintype "passive"))
      (node (ref "J1") (pin "16") (pinfunction "16_16") (pintype "passive"))
      (node (ref "J1") (pin "18") (pinfunction "18_18") (pintype "passive"))
      (node (ref "J1") (pin "20") (pinfunction "20_20") (pintype "passive"))
      (node (ref "J1") (pin "4") (pinfunction "4_4") (pintype "passive"))
      (node (ref "J1") (pin "6") (pinfunction "6_6") (pintype "passive"))
      (node (ref "J1") (pin "8") (pinfunction "8_8") (pintype "passive"))
      (node (ref "K0") (pin "1") (pinfunction "1_1") (pintype "passive"))
      (node (ref "K1") (pin "1") (pinfunction "1_1") (pintype "passive"))
      (node (ref "K2") (pin "1") (pinfunction "1_1") (pintype "passive"))
      (node (ref "P1") (pin "5") (pinfunction "5_5") (pintype "passive"))
      (node (ref "P1") (pin "6") (pinfunction "6_6") (pintype "passive"))
      (node (ref "P9") (pin "4") (pinfunction "4_4") (pintype "passive"))
      (node (ref "Q1") (pin "2") (pinfunction "E_2") (pintype "passive"))
      (node (ref "R10") (pin "1") (pinfunction "1_1") (pintype "passive"))
      (node (ref "R14") (pin "1") (pinfunction "1_1") (pintype "passive"))
      (node (ref "SW1") (pin "2") (pinfunction "2_2") (pintype "passive"))
      (node (ref "U10") (pin "4") (pinfunction "GND_4") (pintype "passive"))
      (node (ref "U11") (pin "1") (pinfunction "A0_1") (pintype "input"))
      (node (ref "U11") (pin "2") (pinfunction "A1_2") (pintype "input"))
      (node (ref "U11") (pin "3") (pinfunction "A2_3") (pintype "input"))
      (node (ref "U11") (pin "4") (pinfunction "GND_4") (pintype "passive"))
      (node (ref "U11") (pin "7") (pinfunction "WP_7") (pintype "passive"))
      (node (ref "U2") (pin "107") (pinfunction "VSS_2_107") (pintype "power_in"))
      (node (ref "U2") (pin "120") (pinfunction "VSS_10_120") (pintype "power_in"))
      (node (ref "U2") (pin "130") (pinfunction "VSS_11_130") (pintype "power_in"))
      (node (ref "U2") (pin "143") (pinfunction "VSS_3_143") (pintype "power_in"))
      (node (ref "U2") (pin "16") (pinfunction "VSS_5_16") (pintype "power_in"))
      (node (ref "U2") (pin "30") (pinfunction "VSSA_30") (pintype "power_in"))
      (node (ref "U2") (pin "31") (pinfunction "VREF-_31") (pintype "power_in"))
      (node (ref "U2") (pin "38") (pinfunction "VSS_4_38") (pintype "power_in"))
      (node (ref "U2") (pin "51") (pinfunction "VSS_6_51") (pintype "power_in"))
      (node (ref "U2") (pin "61") (pinfunction "VSS_7_61") (pintype "power_in"))
      (node (ref "U2") (pin "71") (pinfunction "VSS_1_71") (pintype "power_in"))
      (node (ref "U2") (pin "83") (pinfunction "VSS_8_83") (pintype "power_in"))
      (node (ref "U2") (pin "94") (pinfunction "VSS_9_94") (pintype "power_in"))
      (node (ref "USB_232") (pin "4") (pinfunction "GND_4") (pintype "passive"))
      (node (ref "V1") (pin "1") (pinfunction "GND_1") (pintype "passive"))
    )
    (net (code "123") (name "Net-(D1-K)") (class "Default")
      (node (ref "D1") (pin "2") (pinfunction "K_2") (pintype "passive"))
      (node (ref "IC1") (pin "2") (pinfunction "OUT_2") (pintype "power_in"))
      (node (ref "L1") (pin "1") (pinfunction "1_1") (pintype "passive"))
    )
    (net (code "124") (name "Net-(LED1-A)") (class "Default")
      (node (ref "LED1") (pin "1") (pinfunction "A_1") (pintype "passive"))
      (node (ref "R4") (pin "2") (pinfunction "2_2") (pintype "passive"))
    )
    (net (code "125") (name "Net-(LED2-A)") (class "Default")
      (node (ref "LED2") (pin "1") (pinfunction "A_1") (pintype "passive"))
      (node (ref "R5") (pin "2") (pinfunction "2_2") (pintype "passive"))
    )
    (net (code "126") (name "Net-(P1-Pad3)") (class "Default")
      (node (ref "P1") (pin "3") (pinfunction "3_3") (pintype "passive"))
      (node (ref "R2") (pin "2") (pinfunction "2_2") (pintype "passive"))
    )
    (net (code "127") (name "Net-(P1-Pad4)") (class "Default")
      (node (ref "P1") (pin "4") (pinfunction "4_4") (pintype "passive"))
      (node (ref "R3") (pin "2") (pinfunction "2_2") (pintype "passive"))
    )
    (net (code "128") (name "Net-(Q1-B)") (class "Default")
      (node (ref "Q1") (pin "1") (pinfunction "B_1") (pintype "passive"))
      (node (ref "R1") (pin "1") (pinfunction "1_1") (pintype "passive"))
      (node (ref "R14") (pin "2") (pinfunction "2_2") (pintype "passive"))
    )
    (net (code "129") (name "Net-(Q1-C)") (class "Default")
      (node (ref "LS1") (pin "2") (pinfunction "2_2") (pintype "passive"))
      (node (ref "Q1") (pin "3") (pinfunction "C_3") (pintype "passive"))
    )
    (net (code "130") (name "Net-(U11-SDA)") (class "Default")
      (node (ref "R16") (pin "1") (pinfunction "1_1") (pintype "passive"))
      (node (ref "U11") (pin "5") (pinfunction "SDA_5") (pintype "bidirectional"))
    )
    (net (code "131") (name "Net-(U14-V3)") (class "Default")
      (node (ref "C22") (pin "2") (pinfunction "2_2") (pintype "passive"))
      (node (ref "U14") (pin "4") (pinfunction "V3_4") (pintype "passive"))
    )
    (net (code "132") (name "Net-(U14-XI)") (class "Default")
      (node (ref "C23") (pin "2") (pinfunction "2_2") (pintype "passive"))
      (node (ref "U14") (pin "7") (pinfunction "XI_7") (pintype "passive"))
      (node (ref "Y3") (pin "1") (pinfunction "OSC1_1") (pintype "passive"))
    )
    (net (code "133") (name "Net-(U14-XO)") (class "Default")
      (node (ref "C21") (pin "2") (pinfunction "2_2") (pintype "passive"))
      (node (ref "U14") (pin "8") (pinfunction "XO_8") (pintype "passive"))
      (node (ref "Y3") (pin "2") (pinfunction "OSC2_2") (pintype "passive"))
    )
    (net (code "134") (name "VUSB") (class "Default")
      (node (ref "USB_232") (pin "1") (pinfunction "VCC_1") (pintype "passive"))
    )
    (net (code "135") (name "unconnected-(C8-Pad1)") (class "Default")
      (node (ref "C8") (pin "1") (pinfunction "1_1") (pintype "passive"))
    )
    (net (code "136") (name "unconnected-(C8-Pad2)") (class "Default")
      (node (ref "C8") (pin "2") (pinfunction "2_2") (pintype "passive"))
    )
    (net (code "137") (name "unconnected-(J1-Pad11)") (class "Default")
      (node (ref "J1") (pin "11") (pinfunction "11_11") (pintype "passive+no_connect"))
    )
    (net (code "138") (name "unconnected-(J1-Pad17)") (class "Default")
      (node (ref "J1") (pin "17") (pinfunction "17_17") (pintype "passive+no_connect"))
    )
    (net (code "139") (name "unconnected-(J1-Pad19)") (class "Default")
      (node (ref "J1") (pin "19") (pinfunction "19_19") (pintype "passive+no_connect"))
    )
    (net (code "140") (name "unconnected-(U2B-NC-Pad106)") (class "Default")
      (node (ref "U2") (pin "106") (pinfunction "NC_106") (pintype "passive+no_connect"))
    )
    (net (code "141") (name "unconnected-(U14-CTS#-Pad9)") (class "Default")
      (node (ref "U14") (pin "9") (pinfunction "CTS#_9") (pintype "passive"))
    )
    (net (code "142") (name "unconnected-(U14-DCD#-Pad12)") (class "Default")
      (node (ref "U14") (pin "12") (pinfunction "DCD#_12") (pintype "passive"))
    )
    (net (code "143") (name "unconnected-(U14-DSR#-Pad10)") (class "Default")
      (node (ref "U14") (pin "10") (pinfunction "DSR#_10") (pintype "passive"))
    )
    (net (code "144") (name "unconnected-(U14-DTR#-Pad13)") (class "Default")
      (node (ref "U14") (pin "13") (pinfunction "DTR#_13") (pintype "passive"))
    )
    (net (code "145") (name "unconnected-(U14-GND-Pad1)") (class "Default")
      (node (ref "U14") (pin "1") (pinfunction "GND_1") (pintype "passive"))
    )
    (net (code "146") (name "unconnected-(U14-RI#-Pad11)") (class "Default")
      (node (ref "U14") (pin "11") (pinfunction "RI#_11") (pintype "passive"))
    )
    (net (code "147") (name "unconnected-(U14-RS232-Pad15)") (class "Default")
      (node (ref "U14") (pin "15") (pinfunction "RS232_15") (pintype "passive"))
    )
    (net (code "148") (name "unconnected-(U14-RTS#-Pad14)") (class "Default")
      (node (ref "U14") (pin "14") (pinfunction "RTS#_14") (pintype "passive"))
    )
    (net (code "149") (name "unconnected-(X2-Pad2)") (class "Default")
      (node (ref "X2") (pin "2") (pinfunction "2_2") (pintype "passive"))
    )
    (net (code "150") (name "unconnected-(X2-Pad3)") (class "Default")
      (node (ref "X2") (pin "3") (pinfunction "3_3") (pintype "passive"))
    )
  )
)
